# ten_peg_board_fixed.net
KiCad netlist of a schematic drawn in EAGLE
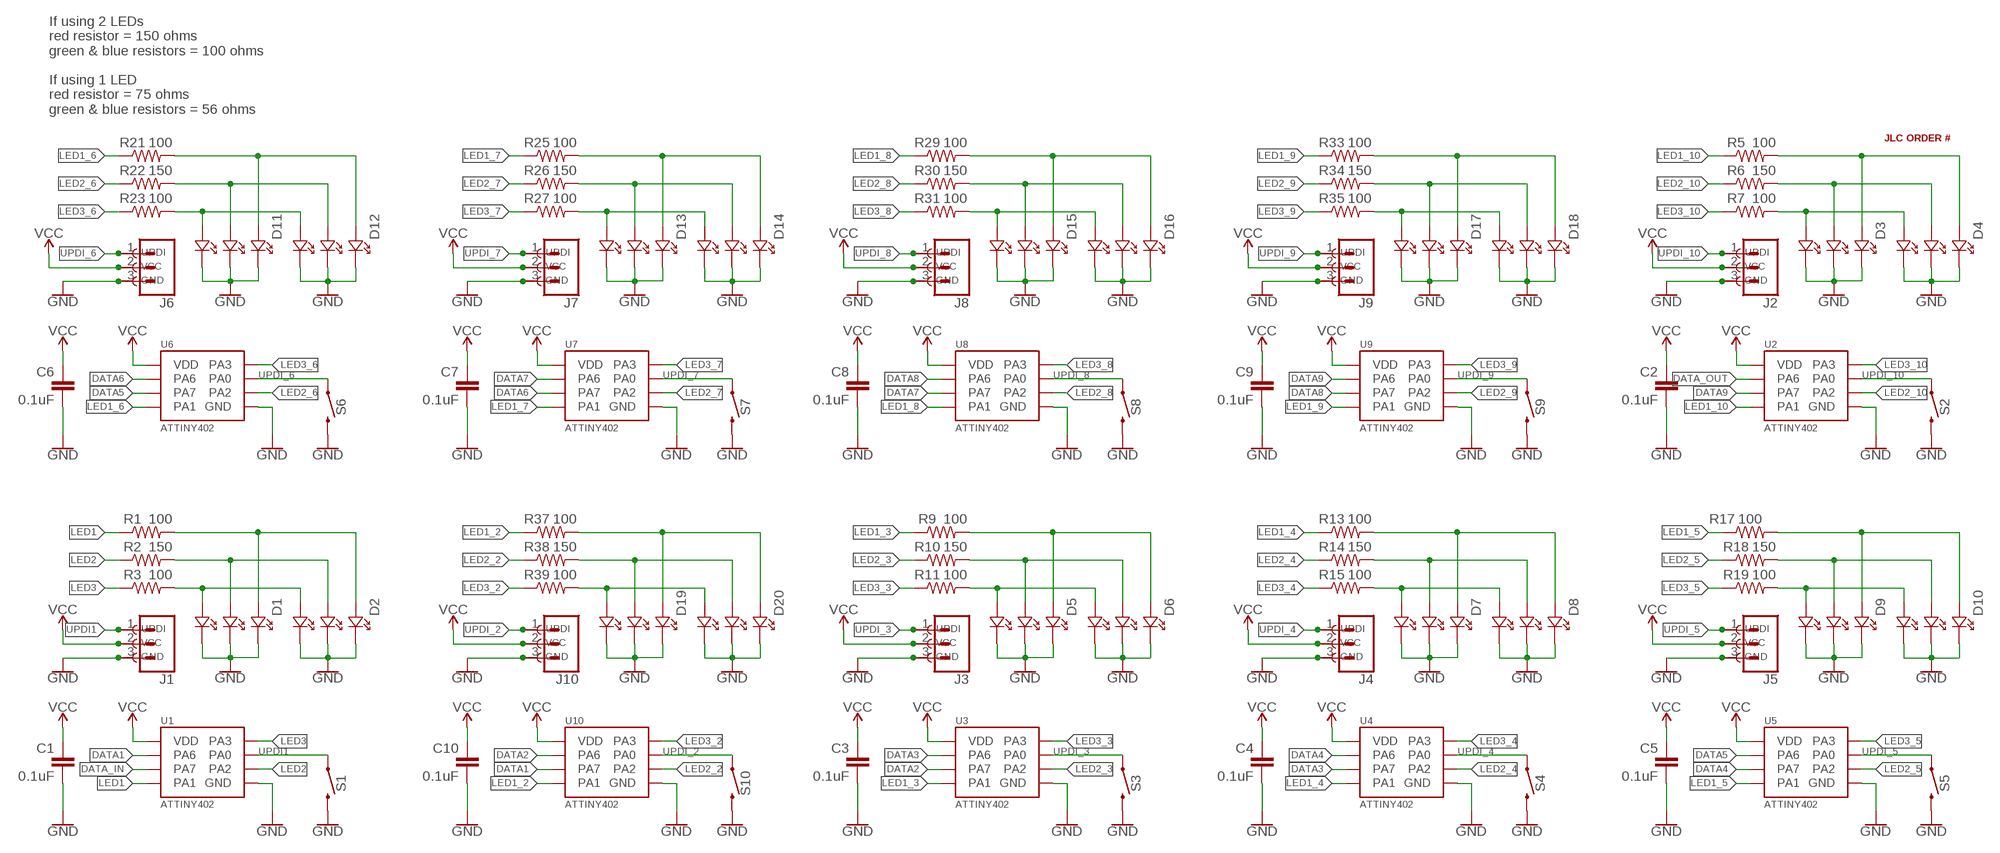
[diagram p0: schematic, sheet 1]

(export (version "E")
  (design (tool "Eeschema 10.0.6"))
  (components
    (comp (ref "C1")
      (value "0.1uF")
      (footprint "eagle-import:0603")
      (libsource (lib "eagle-import") (part "0.1UF-0603-25V-(+80/-20%)"))
    )
    (comp (ref "C2")
      (value "0.1uF")
      (footprint "eagle-import:0603")
      (libsource (lib "eagle-import") (part "0.1UF-0603-25V-(+80/-20%)"))
    )
    (comp (ref "C3")
      (value "0.1uF")
      (footprint "eagle-import:0603")
      (libsource (lib "eagle-import") (part "0.1UF-0603-25V-(+80/-20%)"))
    )
    (comp (ref "C4")
      (value "0.1uF")
      (footprint "eagle-import:0603")
      (libsource (lib "eagle-import") (part "0.1UF-0603-25V-(+80/-20%)"))
    )
    (comp (ref "C5")
      (value "0.1uF")
      (footprint "eagle-import:0603")
      (libsource (lib "eagle-import") (part "0.1UF-0603-25V-(+80/-20%)"))
    )
    (comp (ref "C6")
      (value "0.1uF")
      (footprint "eagle-import:0603")
      (libsource (lib "eagle-import") (part "0.1UF-0603-25V-(+80/-20%)"))
    )
    (comp (ref "C7")
      (value "0.1uF")
      (footprint "eagle-import:0603")
      (libsource (lib "eagle-import") (part "0.1UF-0603-25V-(+80/-20%)"))
    )
    (comp (ref "C8")
      (value "0.1uF")
      (footprint "eagle-import:0603")
      (libsource (lib "eagle-import") (part "0.1UF-0603-25V-(+80/-20%)"))
    )
    (comp (ref "C9")
      (value "0.1uF")
      (footprint "eagle-import:0603")
      (libsource (lib "eagle-import") (part "0.1UF-0603-25V-(+80/-20%)"))
    )
    (comp (ref "C10")
      (value "0.1uF")
      (footprint "eagle-import:0603")
      (libsource (lib "eagle-import") (part "0.1UF-0603-25V-(+80/-20%)"))
    )
    (comp (ref "D1")
      (value "19-337C/RSBHGHC-A88/4T")
      (footprint "eagle-import:6-SMD")
      (libsource (lib "eagle-import") (part "19-337C/RSBHGHC-A88/4T"))
    )
    (comp (ref "D2")
      (value "19-337C/RSBHGHC-A88/4T")
      (footprint "eagle-import:6-SMD")
      (libsource (lib "eagle-import") (part "19-337C/RSBHGHC-A88/4T"))
    )
    (comp (ref "D3")
      (value "19-337C/RSBHGHC-A88/4T")
      (footprint "eagle-import:6-SMD")
      (libsource (lib "eagle-import") (part "19-337C/RSBHGHC-A88/4T"))
    )
    (comp (ref "D4")
      (value "19-337C/RSBHGHC-A88/4T")
      (footprint "eagle-import:6-SMD")
      (libsource (lib "eagle-import") (part "19-337C/RSBHGHC-A88/4T"))
    )
    (comp (ref "D5")
      (value "19-337C/RSBHGHC-A88/4T")
      (footprint "eagle-import:6-SMD")
      (libsource (lib "eagle-import") (part "19-337C/RSBHGHC-A88/4T"))
    )
    (comp (ref "D6")
      (value "19-337C/RSBHGHC-A88/4T")
      (footprint "eagle-import:6-SMD")
      (libsource (lib "eagle-import") (part "19-337C/RSBHGHC-A88/4T"))
    )
    (comp (ref "D7")
      (value "19-337C/RSBHGHC-A88/4T")
      (footprint "eagle-import:6-SMD")
      (libsource (lib "eagle-import") (part "19-337C/RSBHGHC-A88/4T"))
    )
    (comp (ref "D8")
      (value "19-337C/RSBHGHC-A88/4T")
      (footprint "eagle-import:6-SMD")
      (libsource (lib "eagle-import") (part "19-337C/RSBHGHC-A88/4T"))
    )
    (comp (ref "D9")
      (value "19-337C/RSBHGHC-A88/4T")
      (footprint "eagle-import:6-SMD")
      (libsource (lib "eagle-import") (part "19-337C/RSBHGHC-A88/4T"))
    )
    (comp (ref "D10")
      (value "19-337C/RSBHGHC-A88/4T")
      (footprint "eagle-import:6-SMD")
      (libsource (lib "eagle-import") (part "19-337C/RSBHGHC-A88/4T"))
    )
    (comp (ref "D11")
      (value "19-337C/RSBHGHC-A88/4T")
      (footprint "eagle-import:6-SMD")
      (libsource (lib "eagle-import") (part "19-337C/RSBHGHC-A88/4T"))
    )
    (comp (ref "D12")
      (value "19-337C/RSBHGHC-A88/4T")
      (footprint "eagle-import:6-SMD")
      (libsource (lib "eagle-import") (part "19-337C/RSBHGHC-A88/4T"))
    )
    (comp (ref "D13")
      (value "19-337C/RSBHGHC-A88/4T")
      (footprint "eagle-import:6-SMD")
      (libsource (lib "eagle-import") (part "19-337C/RSBHGHC-A88/4T"))
    )
    (comp (ref "D14")
      (value "19-337C/RSBHGHC-A88/4T")
      (footprint "eagle-import:6-SMD")
      (libsource (lib "eagle-import") (part "19-337C/RSBHGHC-A88/4T"))
    )
    (comp (ref "D15")
      (value "19-337C/RSBHGHC-A88/4T")
      (footprint "eagle-import:6-SMD")
      (libsource (lib "eagle-import") (part "19-337C/RSBHGHC-A88/4T"))
    )
    (comp (ref "D16")
      (value "19-337C/RSBHGHC-A88/4T")
      (footprint "eagle-import:6-SMD")
      (libsource (lib "eagle-import") (part "19-337C/RSBHGHC-A88/4T"))
    )
    (comp (ref "D17")
      (value "19-337C/RSBHGHC-A88/4T")
      (footprint "eagle-import:6-SMD")
      (libsource (lib "eagle-import") (part "19-337C/RSBHGHC-A88/4T"))
    )
    (comp (ref "D18")
      (value "19-337C/RSBHGHC-A88/4T")
      (footprint "eagle-import:6-SMD")
      (libsource (lib "eagle-import") (part "19-337C/RSBHGHC-A88/4T"))
    )
    (comp (ref "D19")
      (value "19-337C/RSBHGHC-A88/4T")
      (footprint "eagle-import:6-SMD")
      (libsource (lib "eagle-import") (part "19-337C/RSBHGHC-A88/4T"))
    )
    (comp (ref "D20")
      (value "19-337C/RSBHGHC-A88/4T")
      (footprint "eagle-import:6-SMD")
      (libsource (lib "eagle-import") (part "19-337C/RSBHGHC-A88/4T"))
    )
    (comp (ref "J1")
      (value "CONN_03LOCK_LONGPADS")
      (footprint "eagle-import:1X03_LOCK_LONGPADS")
      (libsource (lib "eagle-import") (part "CONN_03LOCK_LONGPADS"))
    )
    (comp (ref "J2")
      (value "CONN_03LOCK_LONGPADS")
      (footprint "eagle-import:1X03_LOCK_LONGPADS")
      (libsource (lib "eagle-import") (part "CONN_03LOCK_LONGPADS"))
    )
    (comp (ref "J3")
      (value "CONN_03LOCK_LONGPADS")
      (footprint "eagle-import:1X03_LOCK_LONGPADS")
      (libsource (lib "eagle-import") (part "CONN_03LOCK_LONGPADS"))
    )
    (comp (ref "J4")
      (value "CONN_03LOCK_LONGPADS")
      (footprint "eagle-import:1X03_LOCK_LONGPADS")
      (libsource (lib "eagle-import") (part "CONN_03LOCK_LONGPADS"))
    )
    (comp (ref "J5")
      (value "CONN_03LOCK_LONGPADS")
      (footprint "eagle-import:1X03_LOCK_LONGPADS")
      (libsource (lib "eagle-import") (part "CONN_03LOCK_LONGPADS"))
    )
    (comp (ref "J6")
      (value "CONN_03LOCK_LONGPADS")
      (footprint "eagle-import:1X03_LOCK_LONGPADS")
      (libsource (lib "eagle-import") (part "CONN_03LOCK_LONGPADS"))
    )
    (comp (ref "J7")
      (value "CONN_03LOCK_LONGPADS")
      (footprint "eagle-import:1X03_LOCK_LONGPADS")
      (libsource (lib "eagle-import") (part "CONN_03LOCK_LONGPADS"))
    )
    (comp (ref "J8")
      (value "CONN_03LOCK_LONGPADS")
      (footprint "eagle-import:1X03_LOCK_LONGPADS")
      (libsource (lib "eagle-import") (part "CONN_03LOCK_LONGPADS"))
    )
    (comp (ref "J9")
      (value "CONN_03LOCK_LONGPADS")
      (footprint "eagle-import:1X03_LOCK_LONGPADS")
      (libsource (lib "eagle-import") (part "CONN_03LOCK_LONGPADS"))
    )
    (comp (ref "J10")
      (value "CONN_03LOCK_LONGPADS")
      (footprint "eagle-import:1X03_LOCK_LONGPADS")
      (libsource (lib "eagle-import") (part "CONN_03LOCK_LONGPADS"))
    )
    (comp (ref "R1")
      (value "100")
      (footprint "eagle-import:0603")
      (libsource (lib "eagle-import") (part "100OHM-0603-1/4W-5%"))
    )
    (comp (ref "R2")
      (value "150")
      (footprint "eagle-import:0603")
      (libsource (lib "eagle-import") (part "100OHM-0603-1/4W-5%"))
    )
    (comp (ref "R3")
      (value "100")
      (footprint "eagle-import:0603")
      (libsource (lib "eagle-import") (part "100OHM-0603-1/4W-5%"))
    )
    (comp (ref "R5")
      (value "100")
      (footprint "eagle-import:0603")
      (libsource (lib "eagle-import") (part "100OHM-0603-1/4W-5%"))
    )
    (comp (ref "R6")
      (value "150")
      (footprint "eagle-import:0603")
      (libsource (lib "eagle-import") (part "100OHM-0603-1/4W-5%"))
    )
    (comp (ref "R7")
      (value "100")
      (footprint "eagle-import:0603")
      (libsource (lib "eagle-import") (part "100OHM-0603-1/4W-5%"))
    )
    (comp (ref "R9")
      (value "100")
      (footprint "eagle-import:0603")
      (libsource (lib "eagle-import") (part "100OHM-0603-1/4W-5%"))
    )
    (comp (ref "R10")
      (value "150")
      (footprint "eagle-import:0603")
      (libsource (lib "eagle-import") (part "100OHM-0603-1/4W-5%"))
    )
    (comp (ref "R11")
      (value "100")
      (footprint "eagle-import:0603")
      (libsource (lib "eagle-import") (part "100OHM-0603-1/4W-5%"))
    )
    (comp (ref "R13")
      (value "100")
      (footprint "eagle-import:0603")
      (libsource (lib "eagle-import") (part "100OHM-0603-1/4W-5%"))
    )
    (comp (ref "R14")
      (value "150")
      (footprint "eagle-import:0603")
      (libsource (lib "eagle-import") (part "100OHM-0603-1/4W-5%"))
    )
    (comp (ref "R15")
      (value "100")
      (footprint "eagle-import:0603")
      (libsource (lib "eagle-import") (part "100OHM-0603-1/4W-5%"))
    )
    (comp (ref "R17")
      (value "100")
      (footprint "eagle-import:0603")
      (libsource (lib "eagle-import") (part "100OHM-0603-1/4W-5%"))
    )
    (comp (ref "R18")
      (value "150")
      (footprint "eagle-import:0603")
      (libsource (lib "eagle-import") (part "100OHM-0603-1/4W-5%"))
    )
    (comp (ref "R19")
      (value "100")
      (footprint "eagle-import:0603")
      (libsource (lib "eagle-import") (part "100OHM-0603-1/4W-5%"))
    )
    (comp (ref "R21")
      (value "100")
      (footprint "eagle-import:0603")
      (libsource (lib "eagle-import") (part "100OHM-0603-1/4W-5%"))
    )
    (comp (ref "R22")
      (value "150")
      (footprint "eagle-import:0603")
      (libsource (lib "eagle-import") (part "100OHM-0603-1/4W-5%"))
    )
    (comp (ref "R23")
      (value "100")
      (footprint "eagle-import:0603")
      (libsource (lib "eagle-import") (part "100OHM-0603-1/4W-5%"))
    )
    (comp (ref "R25")
      (value "100")
      (footprint "eagle-import:0603")
      (libsource (lib "eagle-import") (part "100OHM-0603-1/4W-5%"))
    )
    (comp (ref "R26")
      (value "150")
      (footprint "eagle-import:0603")
      (libsource (lib "eagle-import") (part "100OHM-0603-1/4W-5%"))
    )
    (comp (ref "R27")
      (value "100")
      (footprint "eagle-import:0603")
      (libsource (lib "eagle-import") (part "100OHM-0603-1/4W-5%"))
    )
    (comp (ref "R29")
      (value "100")
      (footprint "eagle-import:0603")
      (libsource (lib "eagle-import") (part "100OHM-0603-1/4W-5%"))
    )
    (comp (ref "R30")
      (value "150")
      (footprint "eagle-import:0603")
      (libsource (lib "eagle-import") (part "100OHM-0603-1/4W-5%"))
    )
    (comp (ref "R31")
      (value "100")
      (footprint "eagle-import:0603")
      (libsource (lib "eagle-import") (part "100OHM-0603-1/4W-5%"))
    )
    (comp (ref "R33")
      (value "100")
      (footprint "eagle-import:0603")
      (libsource (lib "eagle-import") (part "100OHM-0603-1/4W-5%"))
    )
    (comp (ref "R34")
      (value "150")
      (footprint "eagle-import:0603")
      (libsource (lib "eagle-import") (part "100OHM-0603-1/4W-5%"))
    )
    (comp (ref "R35")
      (value "100")
      (footprint "eagle-import:0603")
      (libsource (lib "eagle-import") (part "100OHM-0603-1/4W-5%"))
    )
    (comp (ref "R37")
      (value "100")
      (footprint "eagle-import:0603")
      (libsource (lib "eagle-import") (part "100OHM-0603-1/4W-5%"))
    )
    (comp (ref "R38")
      (value "150")
      (footprint "eagle-import:0603")
      (libsource (lib "eagle-import") (part "100OHM-0603-1/4W-5%"))
    )
    (comp (ref "R39")
      (value "100")
      (footprint "eagle-import:0603")
      (libsource (lib "eagle-import") (part "100OHM-0603-1/4W-5%"))
    )
    (comp (ref "S1")
      (value "MOMENTARY-SWITCH-SPST-SMD-4.5MM-WINGED")
      (footprint "eagle-import:TACTILE_SWITCH_SMD_4.5MM_WINGED")
      (libsource (lib "eagle-import") (part "MOMENTARY-SWITCH-SPST-SMD-4.5MM-WINGED"))
    )
    (comp (ref "S2")
      (value "MOMENTARY-SWITCH-SPST-SMD-4.5MM-WINGED")
      (footprint "eagle-import:TACTILE_SWITCH_SMD_4.5MM_WINGED")
      (libsource (lib "eagle-import") (part "MOMENTARY-SWITCH-SPST-SMD-4.5MM-WINGED"))
    )
    (comp (ref "S3")
      (value "MOMENTARY-SWITCH-SPST-SMD-4.5MM-WINGED")
      (footprint "eagle-import:TACTILE_SWITCH_SMD_4.5MM_WINGED")
      (libsource (lib "eagle-import") (part "MOMENTARY-SWITCH-SPST-SMD-4.5MM-WINGED"))
    )
    (comp (ref "S4")
      (value "MOMENTARY-SWITCH-SPST-SMD-4.5MM-WINGED")
      (footprint "eagle-import:TACTILE_SWITCH_SMD_4.5MM_WINGED")
      (libsource (lib "eagle-import") (part "MOMENTARY-SWITCH-SPST-SMD-4.5MM-WINGED"))
    )
    (comp (ref "S5")
      (value "MOMENTARY-SWITCH-SPST-SMD-4.5MM-WINGED")
      (footprint "eagle-import:TACTILE_SWITCH_SMD_4.5MM_WINGED")
      (libsource (lib "eagle-import") (part "MOMENTARY-SWITCH-SPST-SMD-4.5MM-WINGED"))
    )
    (comp (ref "S6")
      (value "MOMENTARY-SWITCH-SPST-SMD-4.5MM-WINGED")
      (footprint "eagle-import:TACTILE_SWITCH_SMD_4.5MM_WINGED")
      (libsource (lib "eagle-import") (part "MOMENTARY-SWITCH-SPST-SMD-4.5MM-WINGED"))
    )
    (comp (ref "S7")
      (value "MOMENTARY-SWITCH-SPST-SMD-4.5MM-WINGED")
      (footprint "eagle-import:TACTILE_SWITCH_SMD_4.5MM_WINGED")
      (libsource (lib "eagle-import") (part "MOMENTARY-SWITCH-SPST-SMD-4.5MM-WINGED"))
    )
    (comp (ref "S8")
      (value "MOMENTARY-SWITCH-SPST-SMD-4.5MM-WINGED")
      (footprint "eagle-import:TACTILE_SWITCH_SMD_4.5MM_WINGED")
      (libsource (lib "eagle-import") (part "MOMENTARY-SWITCH-SPST-SMD-4.5MM-WINGED"))
    )
    (comp (ref "S9")
      (value "MOMENTARY-SWITCH-SPST-SMD-4.5MM-WINGED")
      (footprint "eagle-import:TACTILE_SWITCH_SMD_4.5MM_WINGED")
      (libsource (lib "eagle-import") (part "MOMENTARY-SWITCH-SPST-SMD-4.5MM-WINGED"))
    )
    (comp (ref "S10")
      (value "MOMENTARY-SWITCH-SPST-SMD-4.5MM-WINGED")
      (footprint "eagle-import:TACTILE_SWITCH_SMD_4.5MM_WINGED")
      (libsource (lib "eagle-import") (part "MOMENTARY-SWITCH-SPST-SMD-4.5MM-WINGED"))
    )
    (comp (ref "TP1")
      (value "TEST-POINT3X5")
      (footprint "eagle-import:PAD.03X.05")
      (libsource (lib "eagle-import") (part "TEST-POINT3X5"))
    )
    (comp (ref "TP2")
      (value "TEST-POINT3X5")
      (footprint "eagle-import:PAD.03X.05")
      (libsource (lib "eagle-import") (part "TEST-POINT3X5"))
    )
    (comp (ref "TP3")
      (value "TEST-POINT3X5")
      (footprint "eagle-import:PAD.03X.05")
      (libsource (lib "eagle-import") (part "TEST-POINT3X5"))
    )
    (comp (ref "TP4")
      (value "TEST-POINT3X5")
      (footprint "eagle-import:PAD.03X.05")
      (libsource (lib "eagle-import") (part "TEST-POINT3X5"))
    )
    (comp (ref "TP5")
      (value "TEST-POINT3X5")
      (footprint "eagle-import:PAD.03X.05")
      (libsource (lib "eagle-import") (part "TEST-POINT3X5"))
    )
    (comp (ref "TP6")
      (value "TEST-POINT3X5")
      (footprint "eagle-import:PAD.03X.05")
      (libsource (lib "eagle-import") (part "TEST-POINT3X5"))
    )
    (comp (ref "TP7")
      (value "TEST-POINT3X5")
      (footprint "eagle-import:PAD.03X.05")
      (libsource (lib "eagle-import") (part "TEST-POINT3X5"))
    )
    (comp (ref "TP8")
      (value "TEST-POINT3X5")
      (footprint "eagle-import:PAD.03X.05")
      (libsource (lib "eagle-import") (part "TEST-POINT3X5"))
    )
    (comp (ref "TP9")
      (value "TEST-POINT3X5")
      (footprint "eagle-import:PAD.03X.05")
      (libsource (lib "eagle-import") (part "TEST-POINT3X5"))
    )
    (comp (ref "TP10")
      (value "TEST-POINT3X5")
      (footprint "eagle-import:PAD.03X.05")
      (libsource (lib "eagle-import") (part "TEST-POINT3X5"))
    )
    (comp (ref "TP11")
      (value "TEST-POINT3X5")
      (footprint "eagle-import:PAD.03X.05")
      (libsource (lib "eagle-import") (part "TEST-POINT3X5"))
    )
    (comp (ref "TP12")
      (value "TEST-POINT3X5")
      (footprint "eagle-import:PAD.03X.05")
      (libsource (lib "eagle-import") (part "TEST-POINT3X5"))
    )
    (comp (ref "TP13")
      (value "TEST-POINT3X5")
      (footprint "eagle-import:PAD.03X.05")
      (libsource (lib "eagle-import") (part "TEST-POINT3X5"))
    )
    (comp (ref "TP14")
      (value "TEST-POINT3X5")
      (footprint "eagle-import:PAD.03X.05")
      (libsource (lib "eagle-import") (part "TEST-POINT3X5"))
    )
    (comp (ref "TP15")
      (value "TEST-POINT3X5")
      (footprint "eagle-import:PAD.03X.05")
      (libsource (lib "eagle-import") (part "TEST-POINT3X5"))
    )
    (comp (ref "TP16")
      (value "TEST-POINT3X5")
      (footprint "eagle-import:PAD.03X.05")
      (libsource (lib "eagle-import") (part "TEST-POINT3X5"))
    )
    (comp (ref "TP17")
      (value "TEST-POINT3X5")
      (footprint "eagle-import:PAD.03X.05")
      (libsource (lib "eagle-import") (part "TEST-POINT3X5"))
    )
    (comp (ref "TP18")
      (value "TEST-POINT3X5")
      (footprint "eagle-import:PAD.03X.05")
      (libsource (lib "eagle-import") (part "TEST-POINT3X5"))
    )
    (comp (ref "TP19")
      (value "TEST-POINT3X5")
      (footprint "eagle-import:PAD.03X.05")
      (libsource (lib "eagle-import") (part "TEST-POINT3X5"))
    )
    (comp (ref "TP20")
      (value "TEST-POINT3X5")
      (footprint "eagle-import:PAD.03X.05")
      (libsource (lib "eagle-import") (part "TEST-POINT3X5"))
    )
    (comp (ref "TP21")
      (value "TEST-POINT3X5")
      (footprint "eagle-import:PAD.03X.05")
      (libsource (lib "eagle-import") (part "TEST-POINT3X5"))
    )
    (comp (ref "TP22")
      (value "TEST-POINT3X5")
      (footprint "eagle-import:PAD.03X.05")
      (libsource (lib "eagle-import") (part "TEST-POINT3X5"))
    )
    (comp (ref "TP23")
      (value "TEST-POINT3X5")
      (footprint "eagle-import:PAD.03X.05")
      (libsource (lib "eagle-import") (part "TEST-POINT3X5"))
    )
    (comp (ref "TP24")
      (value "TEST-POINT3X5")
      (footprint "eagle-import:PAD.03X.05")
      (libsource (lib "eagle-import") (part "TEST-POINT3X5"))
    )
    (comp (ref "TP25")
      (value "TEST-POINT3X5")
      (footprint "eagle-import:PAD.03X.05")
      (libsource (lib "eagle-import") (part "TEST-POINT3X5"))
    )
    (comp (ref "TP26")
      (value "TEST-POINT3X5")
      (footprint "eagle-import:PAD.03X.05")
      (libsource (lib "eagle-import") (part "TEST-POINT3X5"))
    )
    (comp (ref "TP27")
      (value "TEST-POINT3X5")
      (footprint "eagle-import:PAD.03X.05")
      (libsource (lib "eagle-import") (part "TEST-POINT3X5"))
    )
    (comp (ref "TP28")
      (value "TEST-POINT3X5")
      (footprint "eagle-import:PAD.03X.05")
      (libsource (lib "eagle-import") (part "TEST-POINT3X5"))
    )
    (comp (ref "TP29")
      (value "TEST-POINT3X5")
      (footprint "eagle-import:PAD.03X.05")
      (libsource (lib "eagle-import") (part "TEST-POINT3X5"))
    )
    (comp (ref "TP30")
      (value "TEST-POINT3X5")
      (footprint "eagle-import:PAD.03X.05")
      (libsource (lib "eagle-import") (part "TEST-POINT3X5"))
    )
    (comp (ref "U$1")
      (value "JLC-ORDER-NUMBER")
      (footprint "eagle-import:JLC_ORDER_NUMBER")
      (libsource (lib "eagle-import") (part "JLC-ORDER-NUMBER"))
    )
    (comp (ref "U1")
      (value "ATTINY402")
      (footprint "eagle-import:8-SOIC")
      (libsource (lib "eagle-import") (part "ATTINY402"))
    )
    (comp (ref "U2")
      (value "ATTINY402")
      (footprint "eagle-import:8-SOIC")
      (libsource (lib "eagle-import") (part "ATTINY402"))
    )
    (comp (ref "U3")
      (value "ATTINY402")
      (footprint "eagle-import:8-SOIC")
      (libsource (lib "eagle-import") (part "ATTINY402"))
    )
    (comp (ref "U4")
      (value "ATTINY402")
      (footprint "eagle-import:8-SOIC")
      (libsource (lib "eagle-import") (part "ATTINY402"))
    )
    (comp (ref "U5")
      (value "ATTINY402")
      (footprint "eagle-import:8-SOIC")
      (libsource (lib "eagle-import") (part "ATTINY402"))
    )
    (comp (ref "U6")
      (value "ATTINY402")
      (footprint "eagle-import:8-SOIC")
      (libsource (lib "eagle-import") (part "ATTINY402"))
    )
    (comp (ref "U7")
      (value "ATTINY402")
      (footprint "eagle-import:8-SOIC")
      (libsource (lib "eagle-import") (part "ATTINY402"))
    )
    (comp (ref "U8")
      (value "ATTINY402")
      (footprint "eagle-import:8-SOIC")
      (libsource (lib "eagle-import") (part "ATTINY402"))
    )
    (comp (ref "U9")
      (value "ATTINY402")
      (footprint "eagle-import:8-SOIC")
      (libsource (lib "eagle-import") (part "ATTINY402"))
    )
    (comp (ref "U10")
      (value "ATTINY402")
      (footprint "eagle-import:8-SOIC")
      (libsource (lib "eagle-import") (part "ATTINY402"))
    )
  )
  (nets
    (net (code "1") (name "DATA1") (class "Default")
      (node (ref "U1") (pin "P$2") (pinfunction "PA6_P$2") (pintype "bidirectional"))
      (node (ref "U10") (pin "P$3") (pinfunction "PA7_P$3") (pintype "bidirectional"))
    )
    (net (code "2") (name "DATA2") (class "Default")
      (node (ref "U10") (pin "P$2") (pinfunction "PA6_P$2") (pintype "bidirectional"))
      (node (ref "U3") (pin "P$3") (pinfunction "PA7_P$3") (pintype "bidirectional"))
    )
    (net (code "3") (name "DATA3") (class "Default")
      (node (ref "U3") (pin "P$2") (pinfunction "PA6_P$2") (pintype "bidirectional"))
      (node (ref "U4") (pin "P$3") (pinfunction "PA7_P$3") (pintype "bidirectional"))
    )
    (net (code "4") (name "DATA4") (class "Default")
      (node (ref "U4") (pin "P$2") (pinfunction "PA6_P$2") (pintype "bidirectional"))
      (node (ref "U5") (pin "P$3") (pinfunction "PA7_P$3") (pintype "bidirectional"))
    )
    (net (code "5") (name "DATA5") (class "Default")
      (node (ref "U5") (pin "P$2") (pinfunction "PA6_P$2") (pintype "bidirectional"))
      (node (ref "U6") (pin "P$3") (pinfunction "PA7_P$3") (pintype "bidirectional"))
    )
    (net (code "6") (name "DATA6") (class "Default")
      (node (ref "U6") (pin "P$2") (pinfunction "PA6_P$2") (pintype "bidirectional"))
      (node (ref "U7") (pin "P$3") (pinfunction "PA7_P$3") (pintype "bidirectional"))
    )
    (net (code "7") (name "DATA7") (class "Default")
      (node (ref "U7") (pin "P$2") (pinfunction "PA6_P$2") (pintype "bidirectional"))
      (node (ref "U8") (pin "P$3") (pinfunction "PA7_P$3") (pintype "bidirectional"))
    )
    (net (code "8") (name "DATA8") (class "Default")
      (node (ref "U8") (pin "P$2") (pinfunction "PA6_P$2") (pintype "bidirectional"))
      (node (ref "U9") (pin "P$3") (pinfunction "PA7_P$3") (pintype "bidirectional"))
    )
    (net (code "9") (name "DATA9") (class "Default")
      (node (ref "U2") (pin "P$3") (pinfunction "PA7_P$3") (pintype "bidirectional"))
      (node (ref "U9") (pin "P$2") (pinfunction "PA6_P$2") (pintype "bidirectional"))
    )
    (net (code "10") (name "DATA_IN") (class "Default")
      (node (ref "U1") (pin "P$3") (pinfunction "PA7_P$3") (pintype "bidirectional"))
    )
    (net (code "11") (name "DATA_OUT") (class "Default")
      (node (ref "U2") (pin "P$2") (pinfunction "PA6_P$2") (pintype "bidirectional"))
    )
    (net (code "12") (name "GND") (class "Default")
      (node (ref "C1") (pin "2") (pinfunction "2_2") (pintype "passive"))
      (node (ref "C10") (pin "2") (pinfunction "2_2") (pintype "passive"))
      (node (ref "C2") (pin "2") (pinfunction "2_2") (pintype "passive"))
      (node (ref "C3") (pin "2") (pinfunction "2_2") (pintype "passive"))
      (node (ref "C4") (pin "2") (pinfunction "2_2") (pintype "passive"))
      (node (ref "C5") (pin "2") (pinfunction "2_2") (pintype "passive"))
      (node (ref "C6") (pin "2") (pinfunction "2_2") (pintype "passive"))
      (node (ref "C7") (pin "2") (pinfunction "2_2") (pintype "passive"))
      (node (ref "C8") (pin "2") (pinfunction "2_2") (pintype "passive"))
      (node (ref "C9") (pin "2") (pinfunction "2_2") (pintype "passive"))
      (node (ref "D1") (pin "P$1") (pinfunction "P$1_P$1") (pintype "bidirectional"))
      (node (ref "D1") (pin "P$3") (pinfunction "P$3_P$3") (pintype "bidirectional"))
      (node (ref "D1") (pin "P$5") (pinfunction "P$5_P$5") (pintype "bidirectional"))
      (node (ref "D10") (pin "P$1") (pinfunction "P$1_P$1") (pintype "bidirectional"))
      (node (ref "D10") (pin "P$3") (pinfunction "P$3_P$3") (pintype "bidirectional"))
      (node (ref "D10") (pin "P$5") (pinfunction "P$5_P$5") (pintype "bidirectional"))
      (node (ref "D11") (pin "P$1") (pinfunction "P$1_P$1") (pintype "bidirectional"))
      (node (ref "D11") (pin "P$3") (pinfunction "P$3_P$3") (pintype "bidirectional"))
      (node (ref "D11") (pin "P$5") (pinfunction "P$5_P$5") (pintype "bidirectional"))
      (node (ref "D12") (pin "P$1") (pinfunction "P$1_P$1") (pintype "bidirectional"))
      (node (ref "D12") (pin "P$3") (pinfunction "P$3_P$3") (pintype "bidirectional"))
      (node (ref "D12") (pin "P$5") (pinfunction "P$5_P$5") (pintype "bidirectional"))
      (node (ref "D13") (pin "P$1") (pinfunction "P$1_P$1") (pintype "bidirectional"))
      (node (ref "D13") (pin "P$3") (pinfunction "P$3_P$3") (pintype "bidirectional"))
      (node (ref "D13") (pin "P$5") (pinfunction "P$5_P$5") (pintype "bidirectional"))
      (node (ref "D14") (pin "P$1") (pinfunction "P$1_P$1") (pintype "bidirectional"))
      (node (ref "D14") (pin "P$3") (pinfunction "P$3_P$3") (pintype "bidirectional"))
      (node (ref "D14") (pin "P$5") (pinfunction "P$5_P$5") (pintype "bidirectional"))
      (node (ref "D15") (pin "P$1") (pinfunction "P$1_P$1") (pintype "bidirectional"))
      (node (ref "D15") (pin "P$3") (pinfunction "P$3_P$3") (pintype "bidirectional"))
      (node (ref "D15") (pin "P$5") (pinfunction "P$5_P$5") (pintype "bidirectional"))
      (node (ref "D16") (pin "P$1") (pinfunction "P$1_P$1") (pintype "bidirectional"))
      (node (ref "D16") (pin "P$3") (pinfunction "P$3_P$3") (pintype "bidirectional"))
      (node (ref "D16") (pin "P$5") (pinfunction "P$5_P$5") (pintype "bidirectional"))
      (node (ref "D17") (pin "P$1") (pinfunction "P$1_P$1") (pintype "bidirectional"))
      (node (ref "D17") (pin "P$3") (pinfunction "P$3_P$3") (pintype "bidirectional"))
      (node (ref "D17") (pin "P$5") (pinfunction "P$5_P$5") (pintype "bidirectional"))
      (node (ref "D18") (pin "P$1") (pinfunction "P$1_P$1") (pintype "bidirectional"))
      (node (ref "D18") (pin "P$3") (pinfunction "P$3_P$3") (pintype "bidirectional"))
      (node (ref "D18") (pin "P$5") (pinfunction "P$5_P$5") (pintype "bidirectional"))
      (node (ref "D19") (pin "P$1") (pinfunction "P$1_P$1") (pintype "bidirectional"))
      (node (ref "D19") (pin "P$3") (pinfunction "P$3_P$3") (pintype "bidirectional"))
      (node (ref "D19") (pin "P$5") (pinfunction "P$5_P$5") (pintype "bidirectional"))
      (node (ref "D2") (pin "P$1") (pinfunction "P$1_P$1") (pintype "bidirectional"))
      (node (ref "D2") (pin "P$3") (pinfunction "P$3_P$3") (pintype "bidirectional"))
      (node (ref "D2") (pin "P$5") (pinfunction "P$5_P$5") (pintype "bidirectional"))
      (node (ref "D20") (pin "P$1") (pinfunction "P$1_P$1") (pintype "bidirectional"))
      (node (ref "D20") (pin "P$3") (pinfunction "P$3_P$3") (pintype "bidirectional"))
      (node (ref "D20") (pin "P$5") (pinfunction "P$5_P$5") (pintype "bidirectional"))
      (node (ref "D3") (pin "P$1") (pinfunction "P$1_P$1") (pintype "bidirectional"))
      (node (ref "D3") (pin "P$3") (pinfunction "P$3_P$3") (pintype "bidirectional"))
      (node (ref "D3") (pin "P$5") (pinfunction "P$5_P$5") (pintype "bidirectional"))
      (node (ref "D4") (pin "P$1") (pinfunction "P$1_P$1") (pintype "bidirectional"))
      (node (ref "D4") (pin "P$3") (pinfunction "P$3_P$3") (pintype "bidirectional"))
      (node (ref "D4") (pin "P$5") (pinfunction "P$5_P$5") (pintype "bidirectional"))
      (node (ref "D5") (pin "P$1") (pinfunction "P$1_P$1") (pintype "bidirectional"))
      (node (ref "D5") (pin "P$3") (pinfunction "P$3_P$3") (pintype "bidirectional"))
      (node (ref "D5") (pin "P$5") (pinfunction "P$5_P$5") (pintype "bidirectional"))
      (node (ref "D6") (pin "P$1") (pinfunction "P$1_P$1") (pintype "bidirectional"))
      (node (ref "D6") (pin "P$3") (pinfunction "P$3_P$3") (pintype "bidirectional"))
      (node (ref "D6") (pin "P$5") (pinfunction "P$5_P$5") (pintype "bidirectional"))
      (node (ref "D7") (pin "P$1") (pinfunction "P$1_P$1") (pintype "bidirectional"))
      (node (ref "D7") (pin "P$3") (pinfunction "P$3_P$3") (pintype "bidirectional"))
      (node (ref "D7") (pin "P$5") (pinfunction "P$5_P$5") (pintype "bidirectional"))
      (node (ref "D8") (pin "P$1") (pinfunction "P$1_P$1") (pintype "bidirectional"))
      (node (ref "D8") (pin "P$3") (pinfunction "P$3_P$3") (pintype "bidirectional"))
      (node (ref "D8") (pin "P$5") (pinfunction "P$5_P$5") (pintype "bidirectional"))
      (node (ref "D9") (pin "P$1") (pinfunction "P$1_P$1") (pintype "bidirectional"))
      (node (ref "D9") (pin "P$3") (pinfunction "P$3_P$3") (pintype "bidirectional"))
      (node (ref "D9") (pin "P$5") (pinfunction "P$5_P$5") (pintype "bidirectional"))
      (node (ref "J1") (pin "3") (pinfunction "3_3") (pintype "passive"))
      (node (ref "J10") (pin "3") (pinfunction "3_3") (pintype "passive"))
      (node (ref "J2") (pin "3") (pinfunction "3_3") (pintype "passive"))
      (node (ref "J3") (pin "3") (pinfunction "3_3") (pintype "passive"))
      (node (ref "J4") (pin "3") (pinfunction "3_3") (pintype "passive"))
      (node (ref "J5") (pin "3") (pinfunction "3_3") (pintype "passive"))
      (node (ref "J6") (pin "3") (pinfunction "3_3") (pintype "passive"))
      (node (ref "J7") (pin "3") (pinfunction "3_3") (pintype "passive"))
      (node (ref "J8") (pin "3") (pinfunction "3_3") (pintype "passive"))
      (node (ref "J9") (pin "3") (pinfunction "3_3") (pintype "passive"))
      (node (ref "S1") (pin "1") (pinfunction "2_1") (pintype "passive"))
      (node (ref "S1") (pin "4") (pinfunction "2_4") (pintype "passive"))
      (node (ref "S10") (pin "1") (pinfunction "2_1") (pintype "passive"))
      (node (ref "S10") (pin "4") (pinfunction "2_4") (pintype "passive"))
      (node (ref "S2") (pin "1") (pinfunction "2_1") (pintype "passive"))
      (node (ref "S2") (pin "4") (pinfunction "2_4") (pintype "passive"))
      (node (ref "S3") (pin "1") (pinfunction "2_1") (pintype "passive"))
      (node (ref "S3") (pin "4") (pinfunction "2_4") (pintype "passive"))
      (node (ref "S4") (pin "1") (pinfunction "2_1") (pintype "passive"))
      (node (ref "S4") (pin "4") (pinfunction "2_4") (pintype "passive"))
      (node (ref "S5") (pin "1") (pinfunction "2_1") (pintype "passive"))
      (node (ref "S5") (pin "4") (pinfunction "2_4") (pintype "passive"))
      (node (ref "S6") (pin "1") (pinfunction "2_1") (pintype "passive"))
      (node (ref "S6") (pin "4") (pinfunction "2_4") (pintype "passive"))
      (node (ref "S7") (pin "1") (pinfunction "2_1") (pintype "passive"))
      (node (ref "S7") (pin "4") (pinfunction "2_4") (pintype "passive"))
      (node (ref "S8") (pin "1") (pinfunction "2_1") (pintype "passive"))
      (node (ref "S8") (pin "4") (pinfunction "2_4") (pintype "passive"))
      (node (ref "S9") (pin "1") (pinfunction "2_1") (pintype "passive"))
      (node (ref "S9") (pin "4") (pinfunction "2_4") (pintype "passive"))
      (node (ref "TP12") (pin "P$1") (pinfunction "1_P$1") (pintype "bidirectional"))
      (node (ref "TP15") (pin "P$1") (pinfunction "1_P$1") (pintype "bidirectional"))
      (node (ref "TP18") (pin "P$1") (pinfunction "1_P$1") (pintype "bidirectional"))
      (node (ref "TP21") (pin "P$1") (pinfunction "1_P$1") (pintype "bidirectional"))
      (node (ref "TP24") (pin "P$1") (pinfunction "1_P$1") (pintype "bidirectional"))
      (node (ref "TP27") (pin "P$1") (pinfunction "1_P$1") (pintype "bidirectional"))
      (node (ref "TP3") (pin "P$1") (pinfunction "1_P$1") (pintype "bidirectional"))
      (node (ref "TP30") (pin "P$1") (pinfunction "1_P$1") (pintype "bidirectional"))
      (node (ref "TP6") (pin "P$1") (pinfunction "1_P$1") (pintype "bidirectional"))
      (node (ref "TP9") (pin "P$1") (pinfunction "1_P$1") (pintype "bidirectional"))
      (node (ref "U1") (pin "P$8") (pinfunction "GND_P$8") (pintype "bidirectional"))
      (node (ref "U10") (pin "P$8") (pinfunction "GND_P$8") (pintype "bidirectional"))
      (node (ref "U2") (pin "P$8") (pinfunction "GND_P$8") (pintype "bidirectional"))
      (node (ref "U3") (pin "P$8") (pinfunction "GND_P$8") (pintype "bidirectional"))
      (node (ref "U4") (pin "P$8") (pinfunction "GND_P$8") (pintype "bidirectional"))
      (node (ref "U5") (pin "P$8") (pinfunction "GND_P$8") (pintype "bidirectional"))
      (node (ref "U6") (pin "P$8") (pinfunction "GND_P$8") (pintype "bidirectional"))
      (node (ref "U7") (pin "P$8") (pinfunction "GND_P$8") (pintype "bidirectional"))
      (node (ref "U8") (pin "P$8") (pinfunction "GND_P$8") (pintype "bidirectional"))
      (node (ref "U9") (pin "P$8") (pinfunction "GND_P$8") (pintype "bidirectional"))
    )
    (net (code "13") (name "LED1") (class "Default")
      (node (ref "R1") (pin "1") (pinfunction "1_1") (pintype "passive"))
      (node (ref "U1") (pin "P$4") (pinfunction "PA1_P$4") (pintype "bidirectional"))
    )
    (net (code "14") (name "LED1_2") (class "Default")
      (node (ref "R37") (pin "1") (pinfunction "1_1") (pintype "passive"))
      (node (ref "U10") (pin "P$4") (pinfunction "PA1_P$4") (pintype "bidirectional"))
    )
    (net (code "15") (name "LED1_3") (class "Default")
      (node (ref "R9") (pin "1") (pinfunction "1_1") (pintype "passive"))
      (node (ref "U3") (pin "P$4") (pinfunction "PA1_P$4") (pintype "bidirectional"))
    )
    (net (code "16") (name "LED1_4") (class "Default")
      (node (ref "R13") (pin "1") (pinfunction "1_1") (pintype "passive"))
      (node (ref "U4") (pin "P$4") (pinfunction "PA1_P$4") (pintype "bidirectional"))
    )
    (net (code "17") (name "LED1_5") (class "Default")
      (node (ref "R17") (pin "1") (pinfunction "1_1") (pintype "passive"))
      (node (ref "U5") (pin "P$4") (pinfunction "PA1_P$4") (pintype "bidirectional"))
    )
    (net (code "18") (name "LED1_6") (class "Default")
      (node (ref "R21") (pin "1") (pinfunction "1_1") (pintype "passive"))
      (node (ref "U6") (pin "P$4") (pinfunction "PA1_P$4") (pintype "bidirectional"))
    )
    (net (code "19") (name "LED1_7") (class "Default")
      (node (ref "R25") (pin "1") (pinfunction "1_1") (pintype "passive"))
      (node (ref "U7") (pin "P$4") (pinfunction "PA1_P$4") (pintype "bidirectional"))
    )
    (net (code "20") (name "LED1_8") (class "Default")
      (node (ref "R29") (pin "1") (pinfunction "1_1") (pintype "passive"))
      (node (ref "U8") (pin "P$4") (pinfunction "PA1_P$4") (pintype "bidirectional"))
    )
    (net (code "21") (name "LED1_9") (class "Default")
      (node (ref "R33") (pin "1") (pinfunction "1_1") (pintype "passive"))
      (node (ref "U9") (pin "P$4") (pinfunction "PA1_P$4") (pintype "bidirectional"))
    )
    (net (code "22") (name "LED1_10") (class "Default")
      (node (ref "R5") (pin "1") (pinfunction "1_1") (pintype "passive"))
      (node (ref "U2") (pin "P$4") (pinfunction "PA1_P$4") (pintype "bidirectional"))
    )
    (net (code "23") (name "LED2") (class "Default")
      (node (ref "R2") (pin "1") (pinfunction "1_1") (pintype "passive"))
      (node (ref "U1") (pin "P$5") (pinfunction "PA2_P$5") (pintype "bidirectional"))
    )
    (net (code "24") (name "LED2_2") (class "Default")
      (node (ref "R38") (pin "1") (pinfunction "1_1") (pintype "passive"))
      (node (ref "U10") (pin "P$5") (pinfunction "PA2_P$5") (pintype "bidirectional"))
    )
    (net (code "25") (name "LED2_3") (class "Default")
      (node (ref "R10") (pin "1") (pinfunction "1_1") (pintype "passive"))
      (node (ref "U3") (pin "P$5") (pinfunction "PA2_P$5") (pintype "bidirectional"))
    )
    (net (code "26") (name "LED2_4") (class "Default")
      (node (ref "R14") (pin "1") (pinfunction "1_1") (pintype "passive"))
      (node (ref "U4") (pin "P$5") (pinfunction "PA2_P$5") (pintype "bidirectional"))
    )
    (net (code "27") (name "LED2_5") (class "Default")
      (node (ref "R18") (pin "1") (pinfunction "1_1") (pintype "passive"))
      (node (ref "U5") (pin "P$5") (pinfunction "PA2_P$5") (pintype "bidirectional"))
    )
    (net (code "28") (name "LED2_6") (class "Default")
      (node (ref "R22") (pin "1") (pinfunction "1_1") (pintype "passive"))
      (node (ref "U6") (pin "P$5") (pinfunction "PA2_P$5") (pintype "bidirectional"))
    )
    (net (code "29") (name "LED2_7") (class "Default")
      (node (ref "R26") (pin "1") (pinfunction "1_1") (pintype "passive"))
      (node (ref "U7") (pin "P$5") (pinfunction "PA2_P$5") (pintype "bidirectional"))
    )
    (net (code "30") (name "LED2_8") (class "Default")
      (node (ref "R30") (pin "1") (pinfunction "1_1") (pintype "passive"))
      (node (ref "U8") (pin "P$5") (pinfunction "PA2_P$5") (pintype "bidirectional"))
    )
    (net (code "31") (name "LED2_9") (class "Default")
      (node (ref "R34") (pin "1") (pinfunction "1_1") (pintype "passive"))
      (node (ref "U9") (pin "P$5") (pinfunction "PA2_P$5") (pintype "bidirectional"))
    )
    (net (code "32") (name "LED2_10") (class "Default")
      (node (ref "R6") (pin "1") (pinfunction "1_1") (pintype "passive"))
      (node (ref "U2") (pin "P$5") (pinfunction "PA2_P$5") (pintype "bidirectional"))
    )
    (net (code "33") (name "LED3") (class "Default")
      (node (ref "R3") (pin "1") (pinfunction "1_1") (pintype "passive"))
      (node (ref "U1") (pin "P$7") (pinfunction "PA3_P$7") (pintype "bidirectional"))
    )
    (net (code "34") (name "LED3_2") (class "Default")
      (node (ref "R39") (pin "1") (pinfunction "1_1") (pintype "passive"))
      (node (ref "U10") (pin "P$7") (pinfunction "PA3_P$7") (pintype "bidirectional"))
    )
    (net (code "35") (name "LED3_3") (class "Default")
      (node (ref "R11") (pin "1") (pinfunction "1_1") (pintype "passive"))
      (node (ref "U3") (pin "P$7") (pinfunction "PA3_P$7") (pintype "bidirectional"))
    )
    (net (code "36") (name "LED3_4") (class "Default")
      (node (ref "R15") (pin "1") (pinfunction "1_1") (pintype "passive"))
      (node (ref "U4") (pin "P$7") (pinfunction "PA3_P$7") (pintype "bidirectional"))
    )
    (net (code "37") (name "LED3_5") (class "Default")
      (node (ref "R19") (pin "1") (pinfunction "1_1") (pintype "passive"))
      (node (ref "U5") (pin "P$7") (pinfunction "PA3_P$7") (pintype "bidirectional"))
    )
    (net (code "38") (name "LED3_6") (class "Default")
      (node (ref "R23") (pin "1") (pinfunction "1_1") (pintype "passive"))
      (node (ref "U6") (pin "P$7") (pinfunction "PA3_P$7") (pintype "bidirectional"))
    )
    (net (code "39") (name "LED3_7") (class "Default")
      (node (ref "R27") (pin "1") (pinfunction "1_1") (pintype "passive"))
      (node (ref "U7") (pin "P$7") (pinfunction "PA3_P$7") (pintype "bidirectional"))
    )
    (net (code "40") (name "LED3_8") (class "Default")
      (node (ref "R31") (pin "1") (pinfunction "1_1") (pintype "passive"))
      (node (ref "U8") (pin "P$7") (pinfunction "PA3_P$7") (pintype "bidirectional"))
    )
    (net (code "41") (name "LED3_9") (class "Default")
      (node (ref "R35") (pin "1") (pinfunction "1_1") (pintype "passive"))
      (node (ref "U9") (pin "P$7") (pinfunction "PA3_P$7") (pintype "bidirectional"))
    )
    (net (code "42") (name "LED3_10") (class "Default")
      (node (ref "R7") (pin "1") (pinfunction "1_1") (pintype "passive"))
      (node (ref "U2") (pin "P$7") (pinfunction "PA3_P$7") (pintype "bidirectional"))
    )
    (net (code "43") (name "Net-(D1-PadP$2)") (class "Default")
      (node (ref "D1") (pin "P$2") (pinfunction "P$2_P$2") (pintype "bidirectional"))
      (node (ref "D2") (pin "P$2") (pinfunction "P$2_P$2") (pintype "bidirectional"))
      (node (ref "R1") (pin "2") (pinfunction "2_2") (pintype "passive"))
    )
    (net (code "44") (name "Net-(D1-PadP$4)") (class "Default")
      (node (ref "D1") (pin "P$4") (pinfunction "P$4_P$4") (pintype "bidirectional"))
      (node (ref "D2") (pin "P$4") (pinfunction "P$4_P$4") (pintype "bidirectional"))
      (node (ref "R2") (pin "2") (pinfunction "2_2") (pintype "passive"))
    )
    (net (code "45") (name "Net-(D1-PadP$6)") (class "Default")
      (node (ref "D1") (pin "P$6") (pinfunction "P$6_P$6") (pintype "bidirectional"))
      (node (ref "D2") (pin "P$6") (pinfunction "P$6_P$6") (pintype "bidirectional"))
      (node (ref "R3") (pin "2") (pinfunction "2_2") (pintype "passive"))
    )
    (net (code "46") (name "Net-(D3-PadP$2)") (class "Default")
      (node (ref "D3") (pin "P$2") (pinfunction "P$2_P$2") (pintype "bidirectional"))
      (node (ref "D4") (pin "P$2") (pinfunction "P$2_P$2") (pintype "bidirectional"))
      (node (ref "R5") (pin "2") (pinfunction "2_2") (pintype "passive"))
    )
    (net (code "47") (name "Net-(D3-PadP$4)") (class "Default")
      (node (ref "D3") (pin "P$4") (pinfunction "P$4_P$4") (pintype "bidirectional"))
      (node (ref "D4") (pin "P$4") (pinfunction "P$4_P$4") (pintype "bidirectional"))
      (node (ref "R6") (pin "2") (pinfunction "2_2") (pintype "passive"))
    )
    (net (code "48") (name "Net-(D3-PadP$6)") (class "Default")
      (node (ref "D3") (pin "P$6") (pinfunction "P$6_P$6") (pintype "bidirectional"))
      (node (ref "D4") (pin "P$6") (pinfunction "P$6_P$6") (pintype "bidirectional"))
      (node (ref "R7") (pin "2") (pinfunction "2_2") (pintype "passive"))
    )
    (net (code "49") (name "Net-(D5-PadP$2)") (class "Default")
      (node (ref "D5") (pin "P$2") (pinfunction "P$2_P$2") (pintype "bidirectional"))
      (node (ref "D6") (pin "P$2") (pinfunction "P$2_P$2") (pintype "bidirectional"))
      (node (ref "R9") (pin "2") (pinfunction "2_2") (pintype "passive"))
    )
    (net (code "50") (name "Net-(D5-PadP$4)") (class "Default")
      (node (ref "D5") (pin "P$4") (pinfunction "P$4_P$4") (pintype "bidirectional"))
      (node (ref "D6") (pin "P$4") (pinfunction "P$4_P$4") (pintype "bidirectional"))
      (node (ref "R10") (pin "2") (pinfunction "2_2") (pintype "passive"))
    )
    (net (code "51") (name "Net-(D5-PadP$6)") (class "Default")
      (node (ref "D5") (pin "P$6") (pinfunction "P$6_P$6") (pintype "bidirectional"))
      (node (ref "D6") (pin "P$6") (pinfunction "P$6_P$6") (pintype "bidirectional"))
      (node (ref "R11") (pin "2") (pinfunction "2_2") (pintype "passive"))
    )
    (net (code "52") (name "Net-(D7-PadP$2)") (class "Default")
      (node (ref "D7") (pin "P$2") (pinfunction "P$2_P$2") (pintype "bidirectional"))
      (node (ref "D8") (pin "P$2") (pinfunction "P$2_P$2") (pintype "bidirectional"))
      (node (ref "R13") (pin "2") (pinfunction "2_2") (pintype "passive"))
    )
    (net (code "53") (name "Net-(D7-PadP$4)") (class "Default")
      (node (ref "D7") (pin "P$4") (pinfunction "P$4_P$4") (pintype "bidirectional"))
      (node (ref "D8") (pin "P$4") (pinfunction "P$4_P$4") (pintype "bidirectional"))
      (node (ref "R14") (pin "2") (pinfunction "2_2") (pintype "passive"))
    )
    (net (code "54") (name "Net-(D7-PadP$6)") (class "Default")
      (node (ref "D7") (pin "P$6") (pinfunction "P$6_P$6") (pintype "bidirectional"))
      (node (ref "D8") (pin "P$6") (pinfunction "P$6_P$6") (pintype "bidirectional"))
      (node (ref "R15") (pin "2") (pinfunction "2_2") (pintype "passive"))
    )
    (net (code "55") (name "Net-(D10-PadP$2)") (class "Default")
      (node (ref "D10") (pin "P$2") (pinfunction "P$2_P$2") (pintype "bidirectional"))
      (node (ref "D9") (pin "P$2") (pinfunction "P$2_P$2") (pintype "bidirectional"))
      (node (ref "R17") (pin "2") (pinfunction "2_2") (pintype "passive"))
    )
    (net (code "56") (name "Net-(D10-PadP$4)") (class "Default")
      (node (ref "D10") (pin "P$4") (pinfunction "P$4_P$4") (pintype "bidirectional"))
      (node (ref "D9") (pin "P$4") (pinfunction "P$4_P$4") (pintype "bidirectional"))
      (node (ref "R18") (pin "2") (pinfunction "2_2") (pintype "passive"))
    )
    (net (code "57") (name "Net-(D10-PadP$6)") (class "Default")
      (node (ref "D10") (pin "P$6") (pinfunction "P$6_P$6") (pintype "bidirectional"))
      (node (ref "D9") (pin "P$6") (pinfunction "P$6_P$6") (pintype "bidirectional"))
      (node (ref "R19") (pin "2") (pinfunction "2_2") (pintype "passive"))
    )
    (net (code "58") (name "Net-(D11-PadP$2)") (class "Default")
      (node (ref "D11") (pin "P$2") (pinfunction "P$2_P$2") (pintype "bidirectional"))
      (node (ref "D12") (pin "P$2") (pinfunction "P$2_P$2") (pintype "bidirectional"))
      (node (ref "R21") (pin "2") (pinfunction "2_2") (pintype "passive"))
    )
    (net (code "59") (name "Net-(D11-PadP$4)") (class "Default")
      (node (ref "D11") (pin "P$4") (pinfunction "P$4_P$4") (pintype "bidirectional"))
      (node (ref "D12") (pin "P$4") (pinfunction "P$4_P$4") (pintype "bidirectional"))
      (node (ref "R22") (pin "2") (pinfunction "2_2") (pintype "passive"))
    )
    (net (code "60") (name "Net-(D11-PadP$6)") (class "Default")
      (node (ref "D11") (pin "P$6") (pinfunction "P$6_P$6") (pintype "bidirectional"))
      (node (ref "D12") (pin "P$6") (pinfunction "P$6_P$6") (pintype "bidirectional"))
      (node (ref "R23") (pin "2") (pinfunction "2_2") (pintype "passive"))
    )
    (net (code "61") (name "Net-(D13-PadP$2)") (class "Default")
      (node (ref "D13") (pin "P$2") (pinfunction "P$2_P$2") (pintype "bidirectional"))
      (node (ref "D14") (pin "P$2") (pinfunction "P$2_P$2") (pintype "bidirectional"))
      (node (ref "R25") (pin "2") (pinfunction "2_2") (pintype "passive"))
    )
    (net (code "62") (name "Net-(D13-PadP$4)") (class "Default")
      (node (ref "D13") (pin "P$4") (pinfunction "P$4_P$4") (pintype "bidirectional"))
      (node (ref "D14") (pin "P$4") (pinfunction "P$4_P$4") (pintype "bidirectional"))
      (node (ref "R26") (pin "2") (pinfunction "2_2") (pintype "passive"))
    )
    (net (code "63") (name "Net-(D13-PadP$6)") (class "Default")
      (node (ref "D13") (pin "P$6") (pinfunction "P$6_P$6") (pintype "bidirectional"))
      (node (ref "D14") (pin "P$6") (pinfunction "P$6_P$6") (pintype "bidirectional"))
      (node (ref "R27") (pin "2") (pinfunction "2_2") (pintype "passive"))
    )
    (net (code "64") (name "Net-(D15-PadP$2)") (class "Default")
      (node (ref "D15") (pin "P$2") (pinfunction "P$2_P$2") (pintype "bidirectional"))
      (node (ref "D16") (pin "P$2") (pinfunction "P$2_P$2") (pintype "bidirectional"))
      (node (ref "R29") (pin "2") (pinfunction "2_2") (pintype "passive"))
    )
    (net (code "65") (name "Net-(D15-PadP$4)") (class "Default")
      (node (ref "D15") (pin "P$4") (pinfunction "P$4_P$4") (pintype "bidirectional"))
      (node (ref "D16") (pin "P$4") (pinfunction "P$4_P$4") (pintype "bidirectional"))
      (node (ref "R30") (pin "2") (pinfunction "2_2") (pintype "passive"))
    )
    (net (code "66") (name "Net-(D15-PadP$6)") (class "Default")
      (node (ref "D15") (pin "P$6") (pinfunction "P$6_P$6") (pintype "bidirectional"))
      (node (ref "D16") (pin "P$6") (pinfunction "P$6_P$6") (pintype "bidirectional"))
      (node (ref "R31") (pin "2") (pinfunction "2_2") (pintype "passive"))
    )
    (net (code "67") (name "Net-(D17-PadP$2)") (class "Default")
      (node (ref "D17") (pin "P$2") (pinfunction "P$2_P$2") (pintype "bidirectional"))
      (node (ref "D18") (pin "P$2") (pinfunction "P$2_P$2") (pintype "bidirectional"))
      (node (ref "R33") (pin "2") (pinfunction "2_2") (pintype "passive"))
    )
    (net (code "68") (name "Net-(D17-PadP$4)") (class "Default")
      (node (ref "D17") (pin "P$4") (pinfunction "P$4_P$4") (pintype "bidirectional"))
      (node (ref "D18") (pin "P$4") (pinfunction "P$4_P$4") (pintype "bidirectional"))
      (node (ref "R34") (pin "2") (pinfunction "2_2") (pintype "passive"))
    )
    (net (code "69") (name "Net-(D17-PadP$6)") (class "Default")
      (node (ref "D17") (pin "P$6") (pinfunction "P$6_P$6") (pintype "bidirectional"))
      (node (ref "D18") (pin "P$6") (pinfunction "P$6_P$6") (pintype "bidirectional"))
      (node (ref "R35") (pin "2") (pinfunction "2_2") (pintype "passive"))
    )
    (net (code "70") (name "Net-(D19-PadP$2)") (class "Default")
      (node (ref "D19") (pin "P$2") (pinfunction "P$2_P$2") (pintype "bidirectional"))
      (node (ref "D20") (pin "P$2") (pinfunction "P$2_P$2") (pintype "bidirectional"))
      (node (ref "R37") (pin "2") (pinfunction "2_2") (pintype "passive"))
    )
    (net (code "71") (name "Net-(D19-PadP$4)") (class "Default")
      (node (ref "D19") (pin "P$4") (pinfunction "P$4_P$4") (pintype "bidirectional"))
      (node (ref "D20") (pin "P$4") (pinfunction "P$4_P$4") (pintype "bidirectional"))
      (node (ref "R38") (pin "2") (pinfunction "2_2") (pintype "passive"))
    )
    (net (code "72") (name "Net-(D19-PadP$6)") (class "Default")
      (node (ref "D19") (pin "P$6") (pinfunction "P$6_P$6") (pintype "bidirectional"))
      (node (ref "D20") (pin "P$6") (pinfunction "P$6_P$6") (pintype "bidirectional"))
      (node (ref "R39") (pin "2") (pinfunction "2_2") (pintype "passive"))
    )
    (net (code "73") (name "UPDI1") (class "Default")
      (node (ref "J1") (pin "1") (pinfunction "1_1") (pintype "passive"))
      (node (ref "S1") (pin "2") (pinfunction "1_2") (pintype "passive"))
      (node (ref "S1") (pin "3") (pinfunction "1_3") (pintype "passive"))
      (node (ref "TP25") (pin "P$1") (pinfunction "1_P$1") (pintype "bidirectional"))
      (node (ref "U1") (pin "P$6") (pinfunction "PA0_P$6") (pintype "bidirectional"))
    )
    (net (code "74") (name "UPDI_2") (class "Default")
      (node (ref "J10") (pin "1") (pinfunction "1_1") (pintype "passive"))
      (node (ref "S10") (pin "2") (pinfunction "1_2") (pintype "passive"))
      (node (ref "S10") (pin "3") (pinfunction "1_3") (pintype "passive"))
      (node (ref "TP22") (pin "P$1") (pinfunction "1_P$1") (pintype "bidirectional"))
      (node (ref "U10") (pin "P$6") (pinfunction "PA0_P$6") (pintype "bidirectional"))
    )
    (net (code "75") (name "UPDI_3") (class "Default")
      (node (ref "J3") (pin "1") (pinfunction "1_1") (pintype "passive"))
      (node (ref "S3") (pin "2") (pinfunction "1_2") (pintype "passive"))
      (node (ref "S3") (pin "3") (pinfunction "1_3") (pintype "passive"))
      (node (ref "TP19") (pin "P$1") (pinfunction "1_P$1") (pintype "bidirectional"))
      (node (ref "U3") (pin "P$6") (pinfunction "PA0_P$6") (pintype "bidirectional"))
    )
    (net (code "76") (name "UPDI_4") (class "Default")
      (node (ref "J4") (pin "1") (pinfunction "1_1") (pintype "passive"))
      (node (ref "S4") (pin "2") (pinfunction "1_2") (pintype "passive"))
      (node (ref "S4") (pin "3") (pinfunction "1_3") (pintype "passive"))
      (node (ref "TP16") (pin "P$1") (pinfunction "1_P$1") (pintype "bidirectional"))
      (node (ref "U4") (pin "P$6") (pinfunction "PA0_P$6") (pintype "bidirectional"))
    )
    (net (code "77") (name "UPDI_5") (class "Default")
      (node (ref "J5") (pin "1") (pinfunction "1_1") (pintype "passive"))
      (node (ref "S5") (pin "2") (pinfunction "1_2") (pintype "passive"))
      (node (ref "S5") (pin "3") (pinfunction "1_3") (pintype "passive"))
      (node (ref "TP13") (pin "P$1") (pinfunction "1_P$1") (pintype "bidirectional"))
      (node (ref "U5") (pin "P$6") (pinfunction "PA0_P$6") (pintype "bidirectional"))
    )
    (net (code "78") (name "UPDI_6") (class "Default")
      (node (ref "J6") (pin "1") (pinfunction "1_1") (pintype "passive"))
      (node (ref "S6") (pin "2") (pinfunction "1_2") (pintype "passive"))
      (node (ref "S6") (pin "3") (pinfunction "1_3") (pintype "passive"))
      (node (ref "TP10") (pin "P$1") (pinfunction "1_P$1") (pintype "bidirectional"))
      (node (ref "U6") (pin "P$6") (pinfunction "PA0_P$6") (pintype "bidirectional"))
    )
    (net (code "79") (name "UPDI_7") (class "Default")
      (node (ref "J7") (pin "1") (pinfunction "1_1") (pintype "passive"))
      (node (ref "S7") (pin "2") (pinfunction "1_2") (pintype "passive"))
      (node (ref "S7") (pin "3") (pinfunction "1_3") (pintype "passive"))
      (node (ref "TP7") (pin "P$1") (pinfunction "1_P$1") (pintype "bidirectional"))
      (node (ref "U7") (pin "P$6") (pinfunction "PA0_P$6") (pintype "bidirectional"))
    )
    (net (code "80") (name "UPDI_8") (class "Default")
      (node (ref "J8") (pin "1") (pinfunction "1_1") (pintype "passive"))
      (node (ref "S8") (pin "2") (pinfunction "1_2") (pintype "passive"))
      (node (ref "S8") (pin "3") (pinfunction "1_3") (pintype "passive"))
      (node (ref "TP4") (pin "P$1") (pinfunction "1_P$1") (pintype "bidirectional"))
      (node (ref "U8") (pin "P$6") (pinfunction "PA0_P$6") (pintype "bidirectional"))
    )
    (net (code "81") (name "UPDI_9") (class "Default")
      (node (ref "J9") (pin "1") (pinfunction "1_1") (pintype "passive"))
      (node (ref "S9") (pin "2") (pinfunction "1_2") (pintype "passive"))
      (node (ref "S9") (pin "3") (pinfunction "1_3") (pintype "passive"))
      (node (ref "TP28") (pin "P$1") (pinfunction "1_P$1") (pintype "bidirectional"))
      (node (ref "U9") (pin "P$6") (pinfunction "PA0_P$6") (pintype "bidirectional"))
    )
    (net (code "82") (name "UPDI_10") (class "Default")
      (node (ref "J2") (pin "1") (pinfunction "1_1") (pintype "passive"))
      (node (ref "S2") (pin "2") (pinfunction "1_2") (pintype "passive"))
      (node (ref "S2") (pin "3") (pinfunction "1_3") (pintype "passive"))
      (node (ref "TP1") (pin "P$1") (pinfunction "1_P$1") (pintype "bidirectional"))
      (node (ref "U2") (pin "P$6") (pinfunction "PA0_P$6") (pintype "bidirectional"))
    )
    (net (code "83") (name "VCC") (class "Default")
      (node (ref "C1") (pin "1") (pinfunction "1_1") (pintype "passive"))
      (node (ref "C10") (pin "1") (pinfunction "1_1") (pintype "passive"))
      (node (ref "C2") (pin "1") (pinfunction "1_1") (pintype "passive"))
      (node (ref "C3") (pin "1") (pinfunction "1_1") (pintype "passive"))
      (node (ref "C4") (pin "1") (pinfunction "1_1") (pintype "passive"))
      (node (ref "C5") (pin "1") (pinfunction "1_1") (pintype "passive"))
      (node (ref "C6") (pin "1") (pinfunction "1_1") (pintype "passive"))
      (node (ref "C7") (pin "1") (pinfunction "1_1") (pintype "passive"))
      (node (ref "C8") (pin "1") (pinfunction "1_1") (pintype "passive"))
      (node (ref "C9") (pin "1") (pinfunction "1_1") (pintype "passive"))
      (node (ref "J1") (pin "2") (pinfunction "2_2") (pintype "passive"))
      (node (ref "J10") (pin "2") (pinfunction "2_2") (pintype "passive"))
      (node (ref "J2") (pin "2") (pinfunction "2_2") (pintype "passive"))
      (node (ref "J3") (pin "2") (pinfunction "2_2") (pintype "passive"))
      (node (ref "J4") (pin "2") (pinfunction "2_2") (pintype "passive"))
      (node (ref "J5") (pin "2") (pinfunction "2_2") (pintype "passive"))
      (node (ref "J6") (pin "2") (pinfunction "2_2") (pintype "passive"))
      (node (ref "J7") (pin "2") (pinfunction "2_2") (pintype "passive"))
      (node (ref "J8") (pin "2") (pinfunction "2_2") (pintype "passive"))
      (node (ref "J9") (pin "2") (pinfunction "2_2") (pintype "passive"))
      (node (ref "TP11") (pin "P$1") (pinfunction "1_P$1") (pintype "bidirectional"))
      (node (ref "TP14") (pin "P$1") (pinfunction "1_P$1") (pintype "bidirectional"))
      (node (ref "TP17") (pin "P$1") (pinfunction "1_P$1") (pintype "bidirectional"))
      (node (ref "TP2") (pin "P$1") (pinfunction "1_P$1") (pintype "bidirectional"))
      (node (ref "TP20") (pin "P$1") (pinfunction "1_P$1") (pintype "bidirectional"))
      (node (ref "TP23") (pin "P$1") (pinfunction "1_P$1") (pintype "bidirectional"))
      (node (ref "TP26") (pin "P$1") (pinfunction "1_P$1") (pintype "bidirectional"))
      (node (ref "TP29") (pin "P$1") (pinfunction "1_P$1") (pintype "bidirectional"))
      (node (ref "TP5") (pin "P$1") (pinfunction "1_P$1") (pintype "bidirectional"))
      (node (ref "TP8") (pin "P$1") (pinfunction "1_P$1") (pintype "bidirectional"))
      (node (ref "U1") (pin "P$1") (pinfunction "VDD_P$1") (pintype "bidirectional"))
      (node (ref "U10") (pin "P$1") (pinfunction "VDD_P$1") (pintype "bidirectional"))
      (node (ref "U2") (pin "P$1") (pinfunction "VDD_P$1") (pintype "bidirectional"))
      (node (ref "U3") (pin "P$1") (pinfunction "VDD_P$1") (pintype "bidirectional"))
      (node (ref "U4") (pin "P$1") (pinfunction "VDD_P$1") (pintype "bidirectional"))
      (node (ref "U5") (pin "P$1") (pinfunction "VDD_P$1") (pintype "bidirectional"))
      (node (ref "U6") (pin "P$1") (pinfunction "VDD_P$1") (pintype "bidirectional"))
      (node (ref "U7") (pin "P$1") (pinfunction "VDD_P$1") (pintype "bidirectional"))
      (node (ref "U8") (pin "P$1") (pinfunction "VDD_P$1") (pintype "bidirectional"))
      (node (ref "U9") (pin "P$1") (pinfunction "VDD_P$1") (pintype "bidirectional"))
    )
  )
)
